# hacksaw_r0.net
KiCad netlist of a schematic drawn in EAGLE
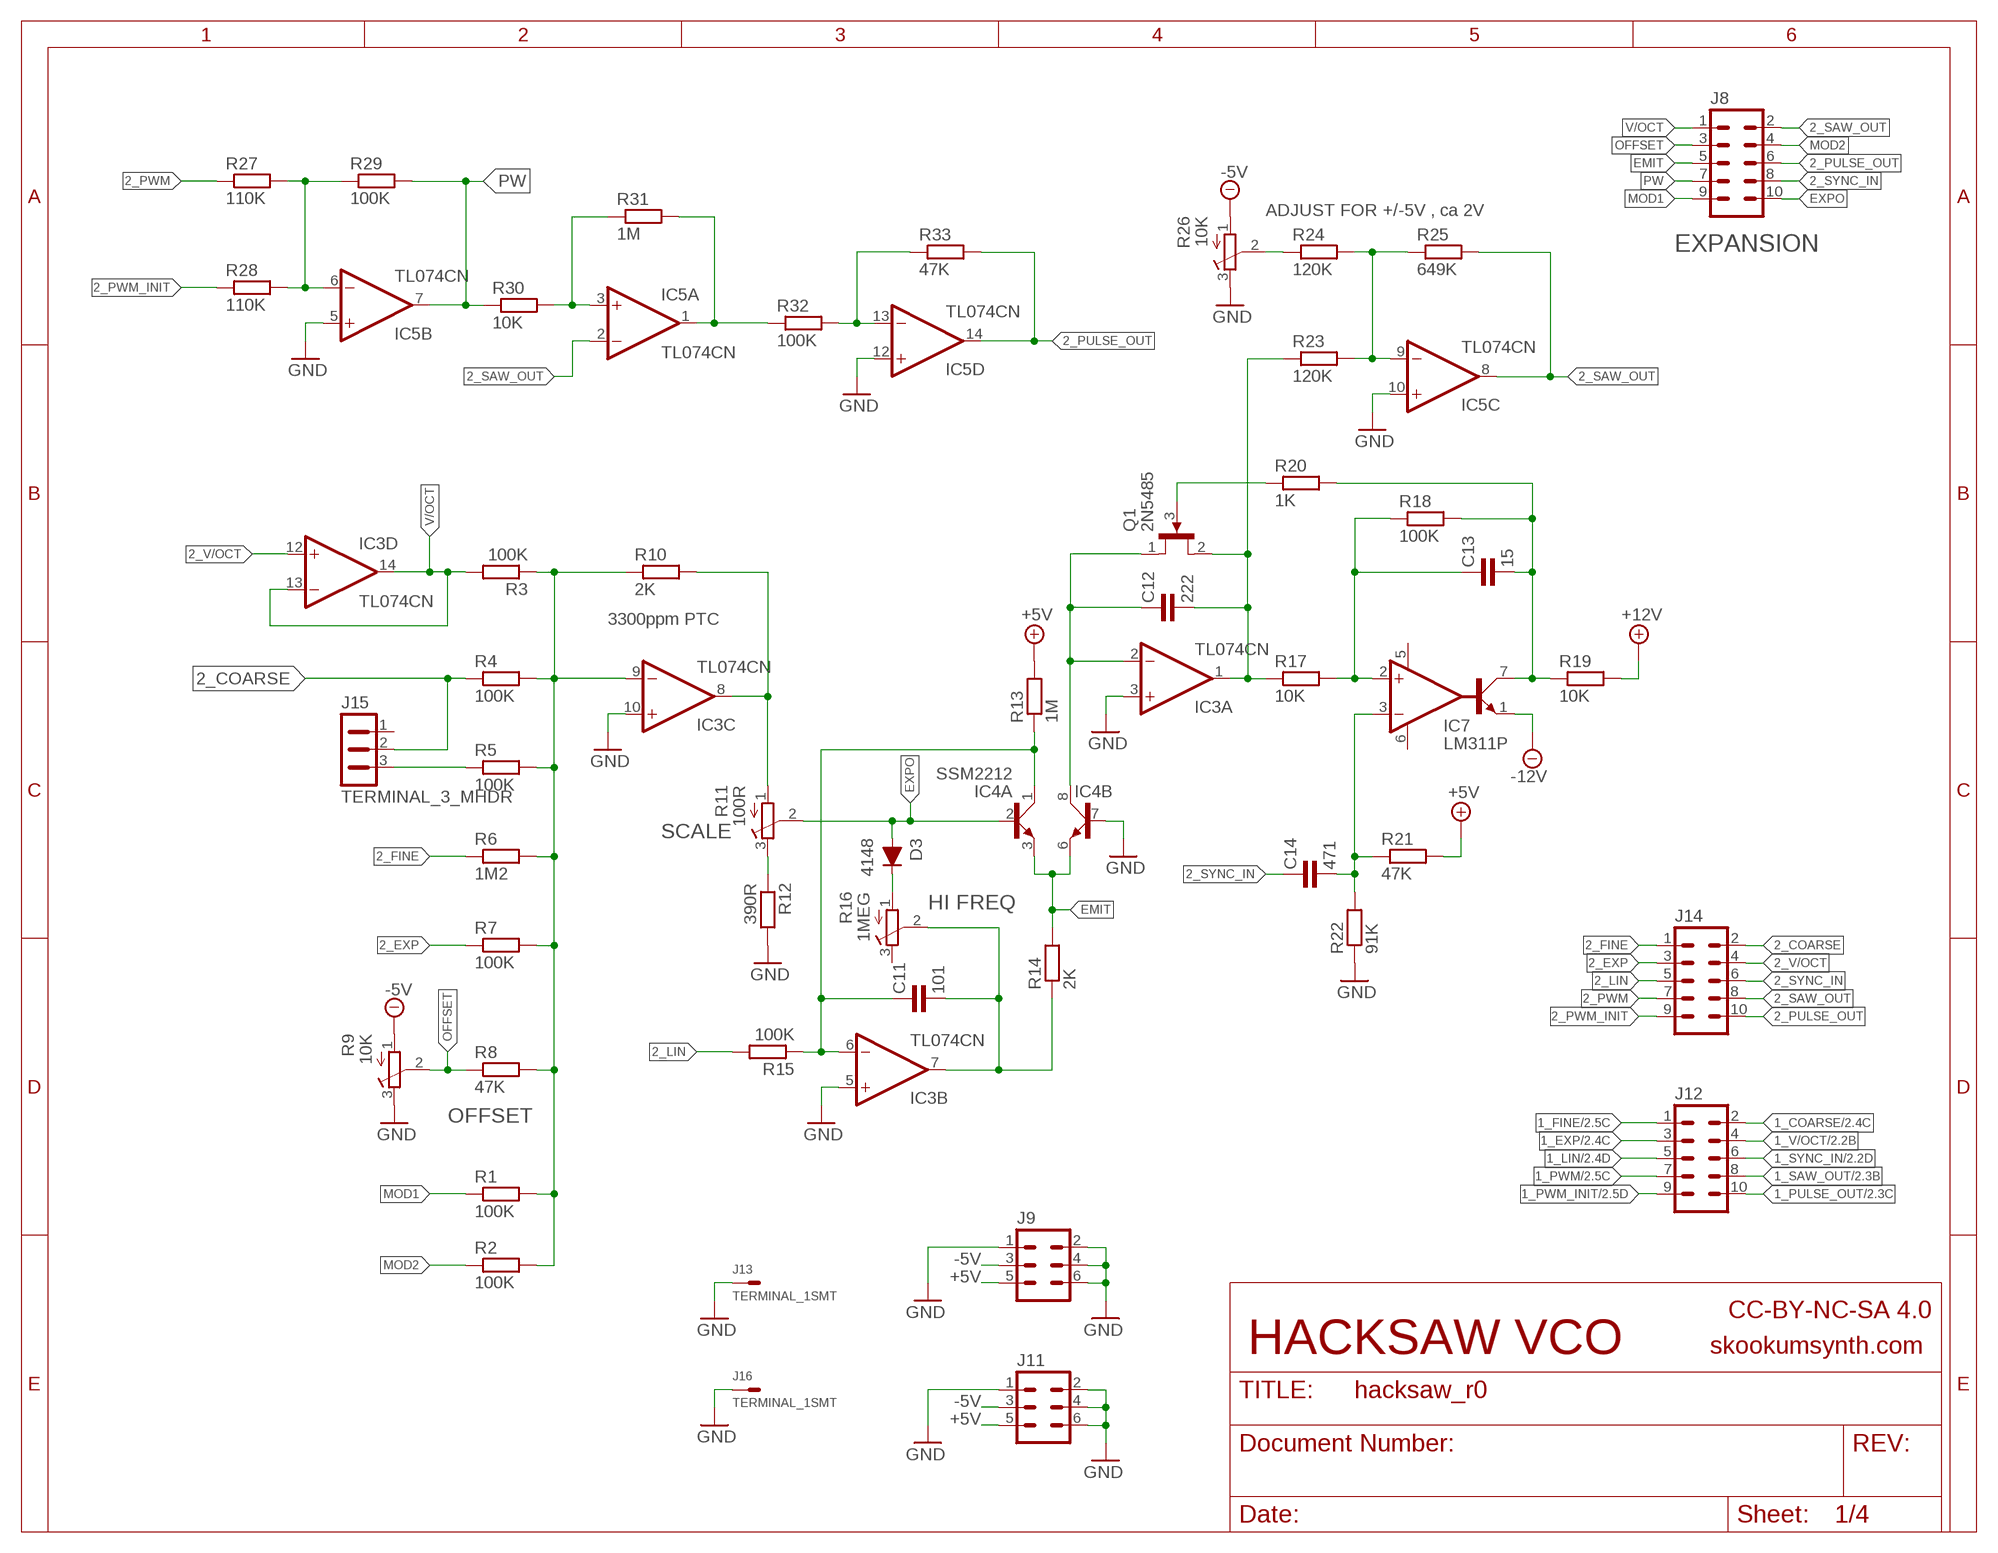
[diagram p0: schematic, sheet 1]
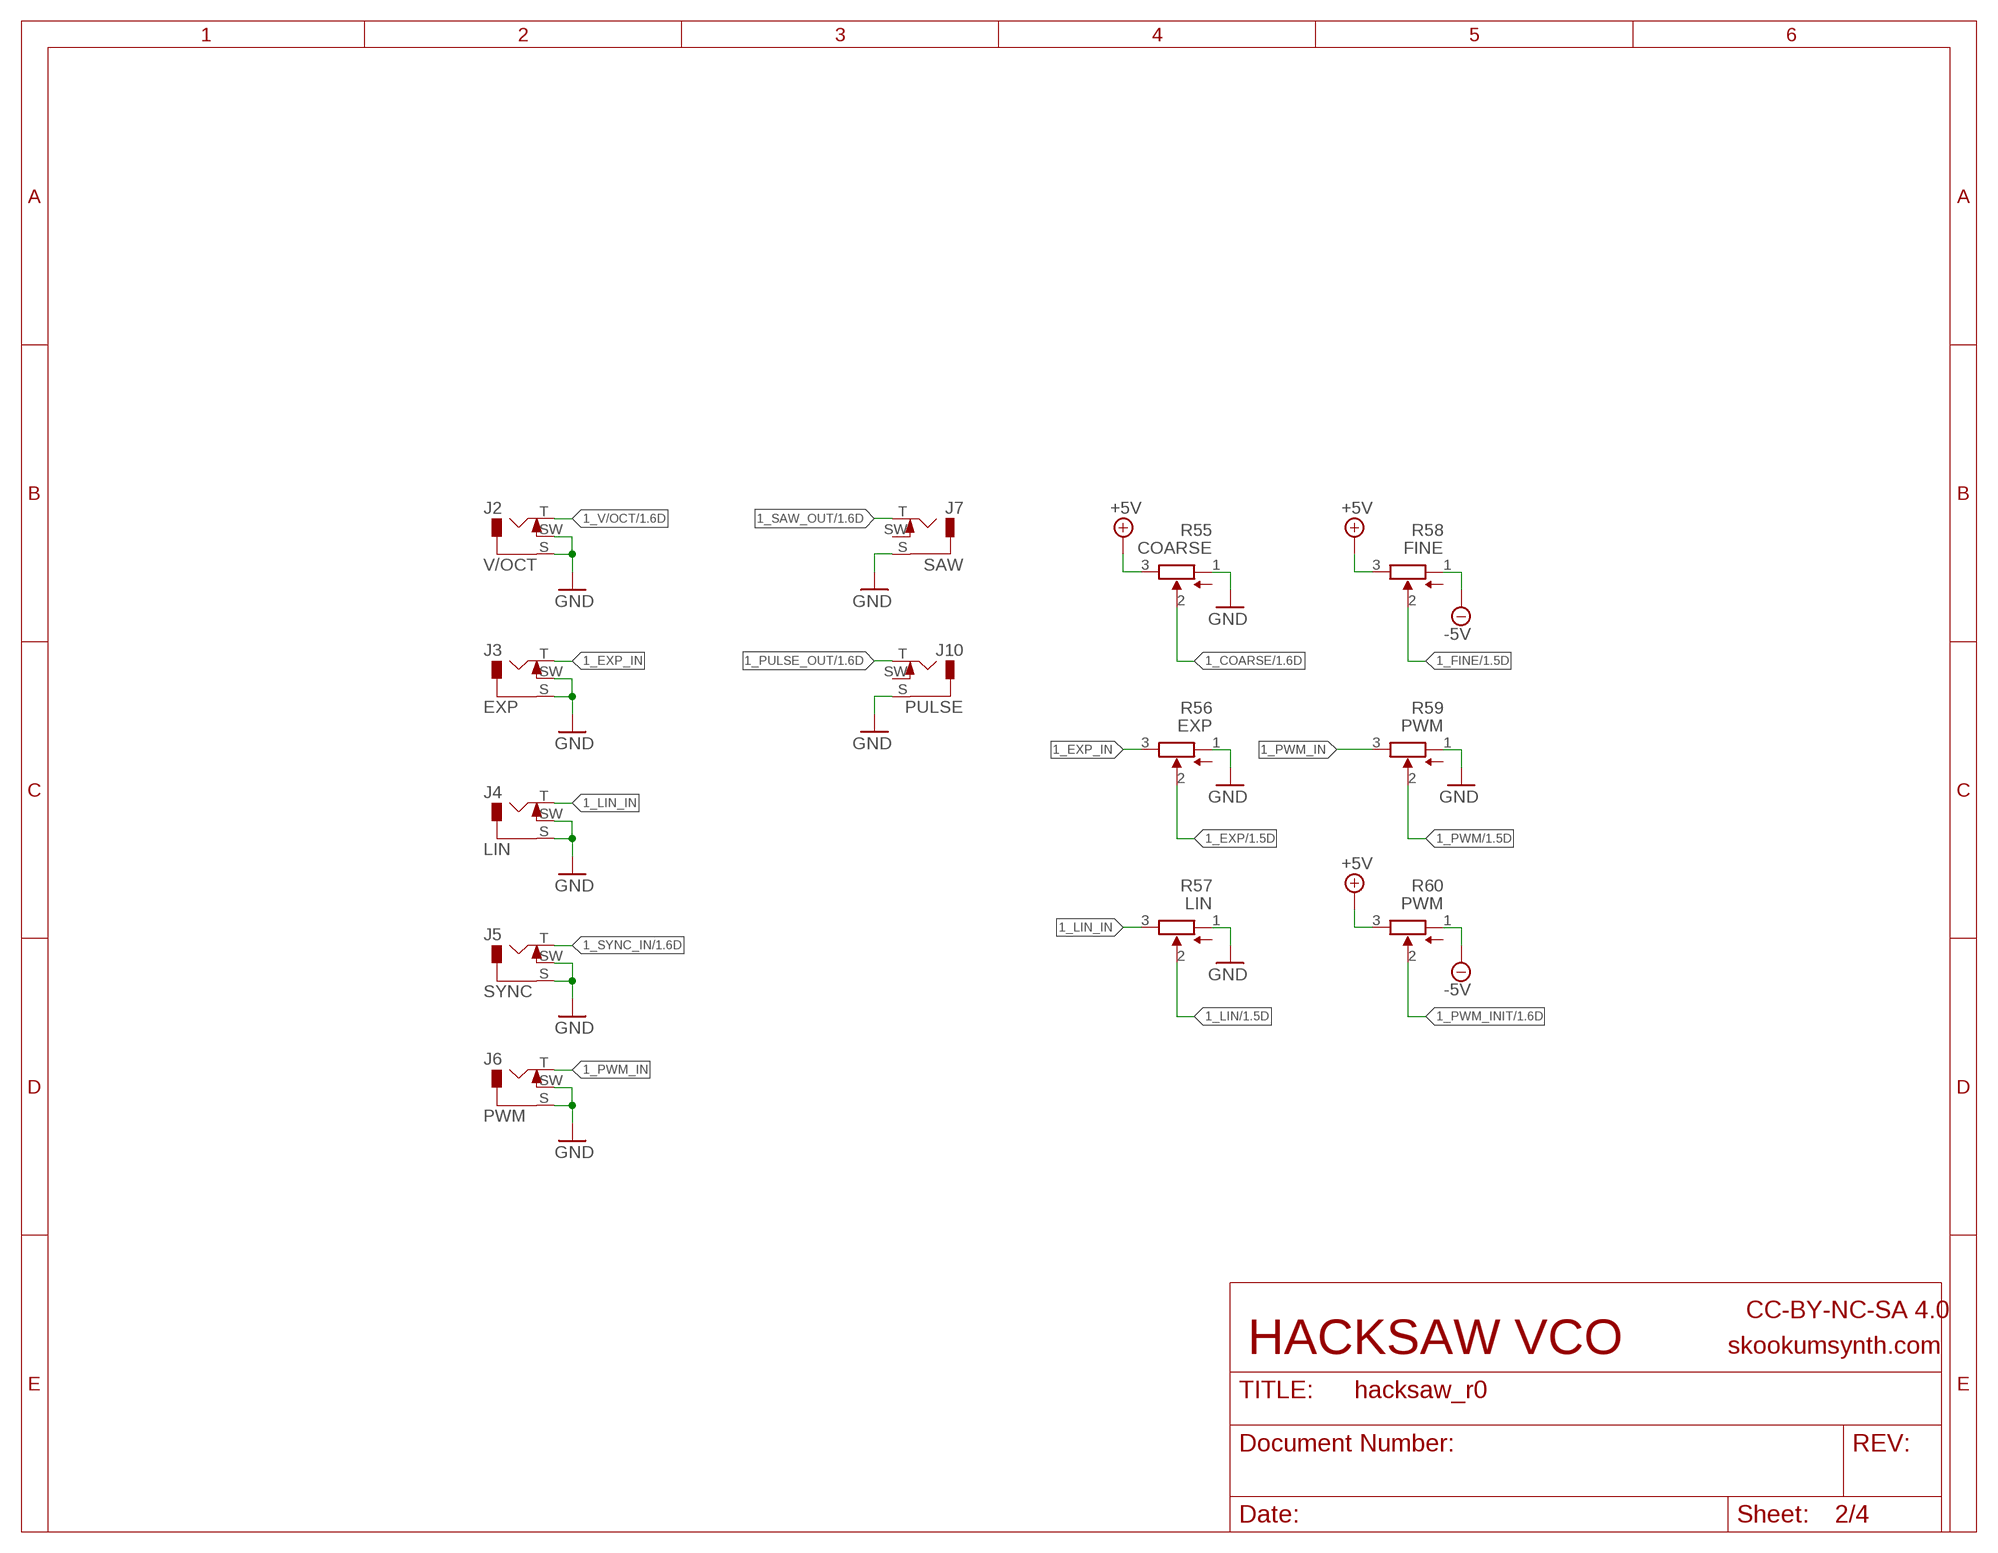
[diagram p1: schematic, sheet 2]
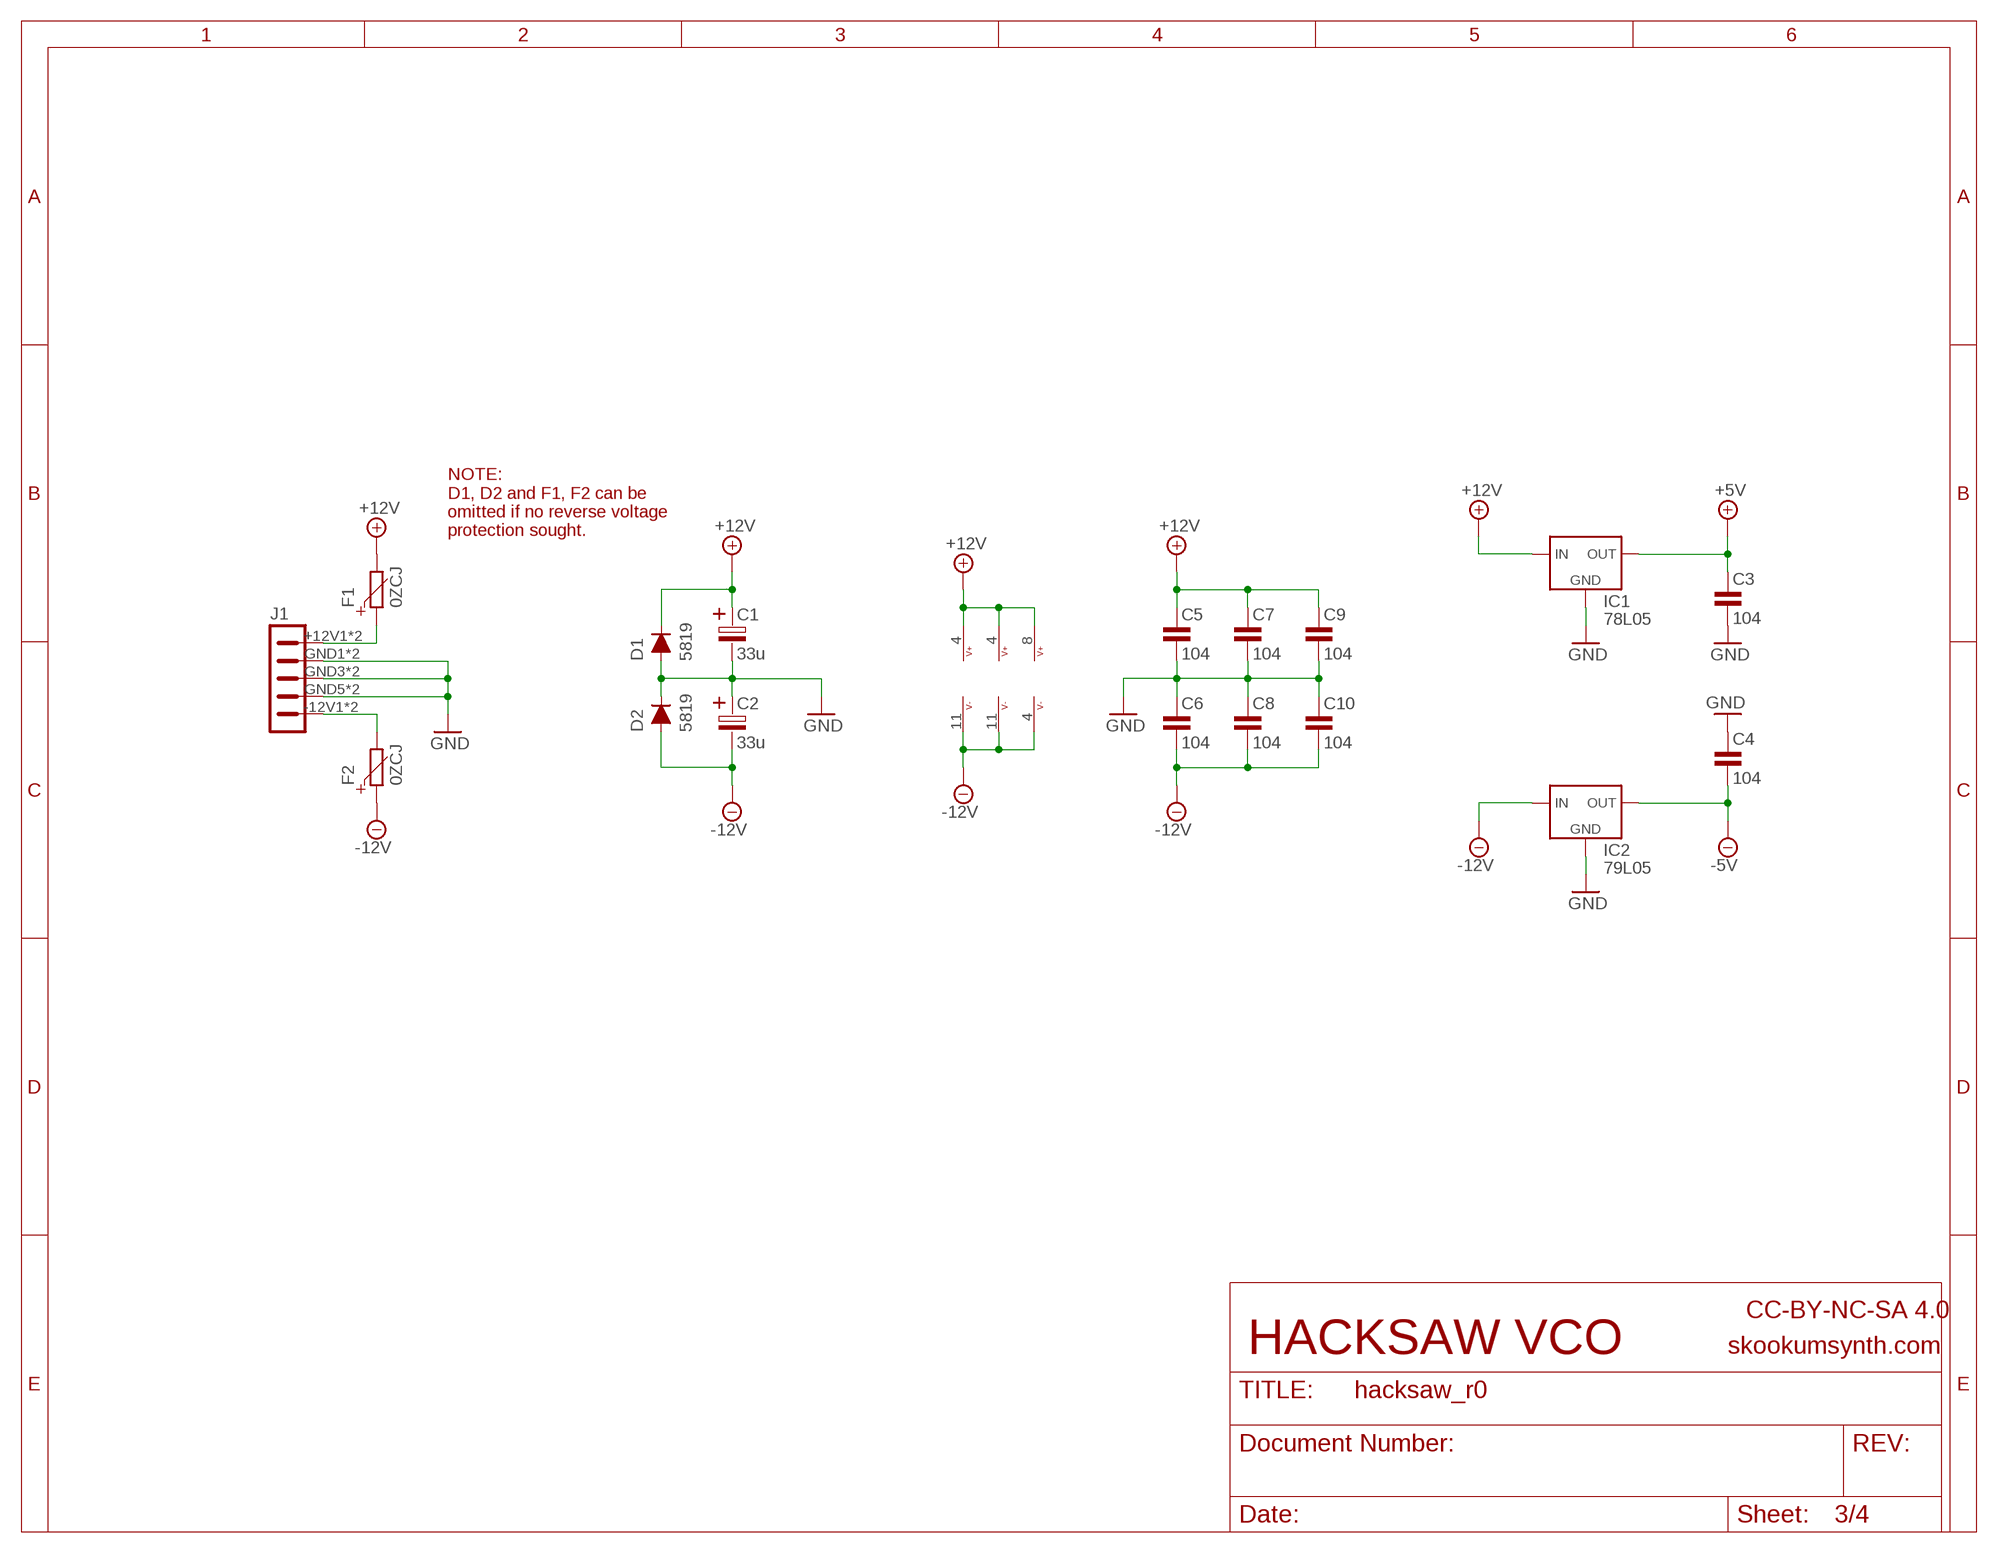
[diagram p2: schematic, sheet 3]
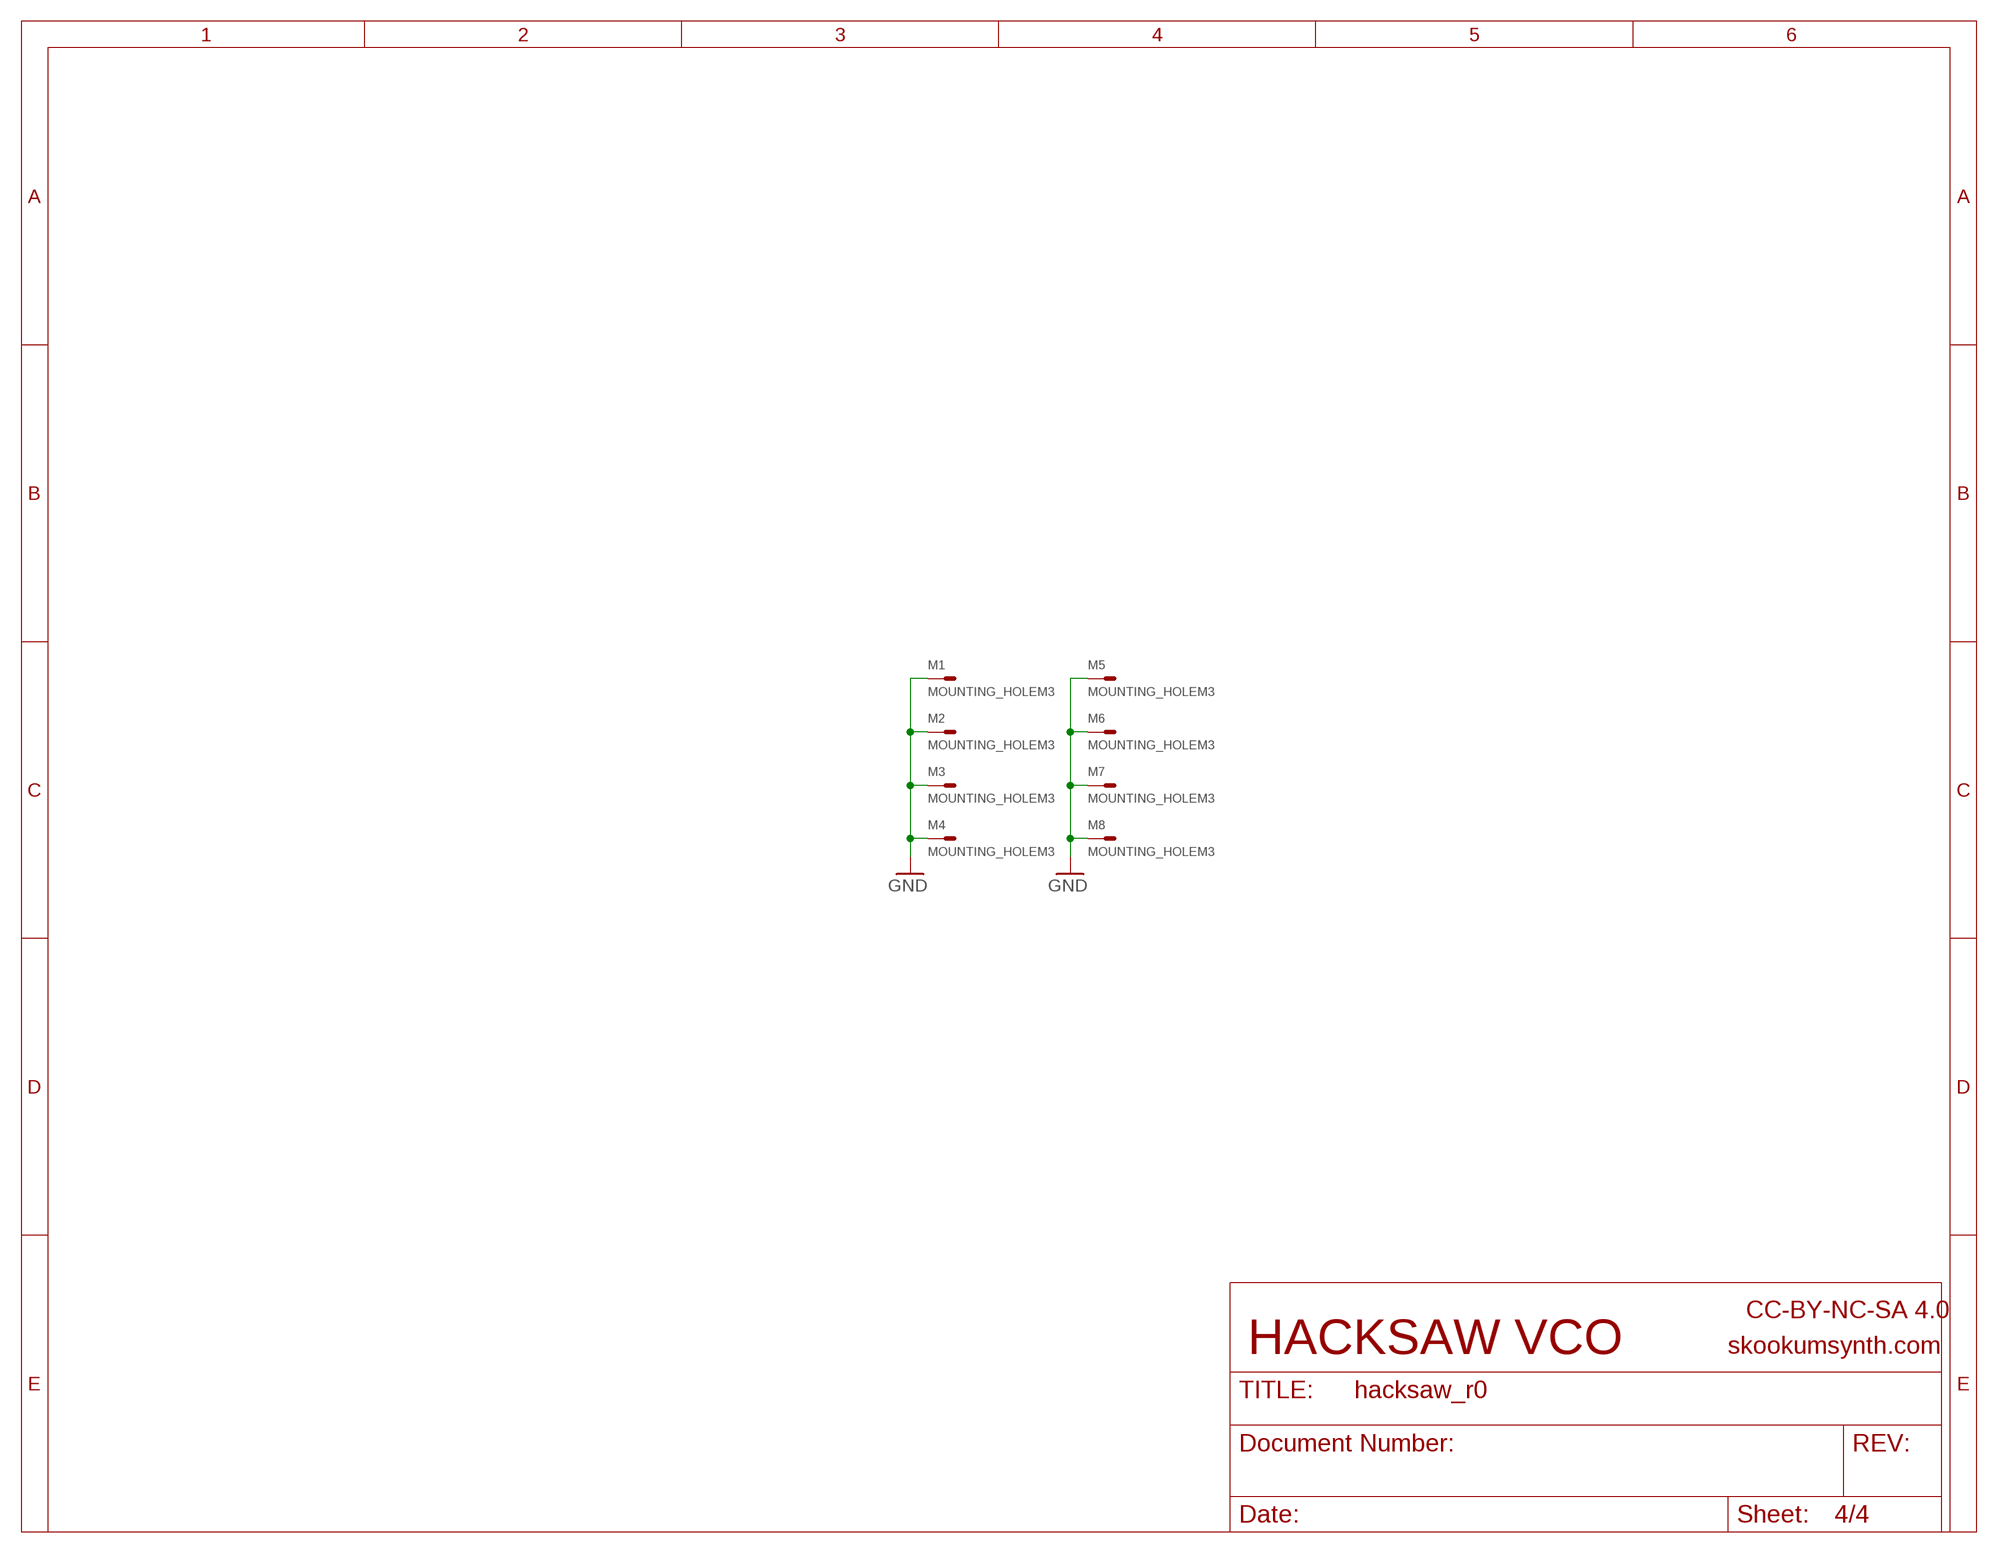
[diagram p3: schematic, sheet 4]

(export (version "E")
  (design (tool "Eeschema 10.0.6"))
  (components
    (comp (ref "C11")
      (value "101")
      (footprint "eagle-import:0805")
      (libsource (lib "eagle-import") (part "CAP_0805"))
    )
    (comp (ref "C12")
      (value "222")
      (footprint "eagle-import:PHE450")
      (libsource (lib "eagle-import") (part "CAP_PHE450"))
    )
    (comp (ref "C13")
      (value "15")
      (footprint "eagle-import:0805")
      (libsource (lib "eagle-import") (part "CAP_0805"))
    )
    (comp (ref "C14")
      (value "471")
      (footprint "eagle-import:0805")
      (libsource (lib "eagle-import") (part "CAP_0805"))
    )
    (comp (ref "D3")
      (value "4148")
      (footprint "eagle-import:SOD123")
      (libsource (lib "eagle-import") (part "DIODE_RECT_SOD123"))
    )
    (comp (ref "IC3")
      (value "TL074CN")
      (footprint "eagle-import:DIL14")
      (libsource (lib "eagle-import") (part "OPAMP_QUAD_DIL14"))
    )
    (comp (ref "IC4")
      (value "SSM2212")
      (footprint "eagle-import:DIL8")
      (libsource (lib "eagle-import") (part "SSM2212"))
    )
    (comp (ref "IC5")
      (value "TL074CN")
      (footprint "eagle-import:DIL14")
      (libsource (lib "eagle-import") (part "OPAMP_QUAD_DIL14"))
    )
    (comp (ref "IC7")
      (value "LM311P")
      (footprint "eagle-import:DIL8")
      (libsource (lib "eagle-import") (part "LM311P"))
    )
    (comp (ref "J8")
      (value "CONN_HDR_5X21")
      (footprint "eagle-import:HDR_M_5X2")
      (libsource (lib "eagle-import") (part "CONN_HDR_5X21"))
    )
    (comp (ref "J9")
      (value "CONN_HDR_3X21")
      (footprint "eagle-import:HDR_M_3X2")
      (libsource (lib "eagle-import") (part "CONN_HDR_3X21"))
    )
    (comp (ref "J11")
      (value "CONN_HDR_3X22")
      (footprint "eagle-import:HDR_M_3X2_REAR")
      (libsource (lib "eagle-import") (part "CONN_HDR_3X22"))
    )
    (comp (ref "J12")
      (value "CONN_HDR_5X22")
      (footprint "eagle-import:HDR_M_5X2_REAR")
      (libsource (lib "eagle-import") (part "CONN_HDR_5X22"))
    )
    (comp (ref "J13")
      (value "TERMINAL_1SMT")
      (footprint "eagle-import:FP_GND")
      (libsource (lib "eagle-import") (part "TERMINAL_1SMT"))
    )
    (comp (ref "J14")
      (value "CONN_HDR_5X21")
      (footprint "eagle-import:HDR_M_5X2")
      (libsource (lib "eagle-import") (part "CONN_HDR_5X21"))
    )
    (comp (ref "J15")
      (value "TERMINAL_3_MHDR")
      (footprint "eagle-import:HDR_M_3")
      (libsource (lib "eagle-import") (part "TERMINAL_3_MHDR"))
    )
    (comp (ref "J16")
      (value "TERMINAL_1SMT")
      (footprint "eagle-import:FP_GND")
      (libsource (lib "eagle-import") (part "TERMINAL_1SMT"))
    )
    (comp (ref "Q1")
      (value "2N5485")
      (footprint "eagle-import:TO-92_2")
      (libsource (lib "eagle-import") (part "NJFET_2N5485"))
    )
    (comp (ref "R1")
      (value "100K")
      (footprint "eagle-import:0805")
      (libsource (lib "eagle-import") (part "RESISTOR_0805"))
    )
    (comp (ref "R2")
      (value "100K")
      (footprint "eagle-import:0805")
      (libsource (lib "eagle-import") (part "RESISTOR_0805"))
    )
    (comp (ref "R3")
      (value "100K")
      (footprint "eagle-import:0805")
      (libsource (lib "eagle-import") (part "RESISTOR_0805"))
    )
    (comp (ref "R4")
      (value "100K")
      (footprint "eagle-import:0805")
      (libsource (lib "eagle-import") (part "RESISTOR_0805"))
    )
    (comp (ref "R5")
      (value "100K")
      (footprint "eagle-import:0805")
      (libsource (lib "eagle-import") (part "RESISTOR_0805"))
    )
    (comp (ref "R6")
      (value "1M2")
      (footprint "eagle-import:0805")
      (libsource (lib "eagle-import") (part "RESISTOR_0805"))
    )
    (comp (ref "R7")
      (value "100K")
      (footprint "eagle-import:0805")
      (libsource (lib "eagle-import") (part "RESISTOR_0805"))
    )
    (comp (ref "R8")
      (value "47K")
      (footprint "eagle-import:0805")
      (libsource (lib "eagle-import") (part "RESISTOR_0805"))
    )
    (comp (ref "R9")
      (value "10K")
      (footprint "eagle-import:PV36W")
      (libsource (lib "eagle-import") (part "RESISTOR_TRIM_PV36W"))
    )
    (comp (ref "R10")
      (value "2K")
      (footprint "eagle-import:RESISTOR_TH_1_4W")
      (libsource (lib "eagle-import") (part "RESISTOR_1/4W"))
    )
    (comp (ref "R11")
      (value "100R")
      (footprint "eagle-import:PV36W")
      (libsource (lib "eagle-import") (part "RESISTOR_TRIM_PV36W"))
    )
    (comp (ref "R12")
      (value "390R")
      (footprint "eagle-import:0805")
      (libsource (lib "eagle-import") (part "RESISTOR_0805"))
    )
    (comp (ref "R13")
      (value "1M")
      (footprint "eagle-import:0805")
      (libsource (lib "eagle-import") (part "RESISTOR_0805"))
    )
    (comp (ref "R14")
      (value "2K")
      (footprint "eagle-import:0805")
      (libsource (lib "eagle-import") (part "RESISTOR_0805"))
    )
    (comp (ref "R15")
      (value "100K")
      (footprint "eagle-import:0805")
      (libsource (lib "eagle-import") (part "RESISTOR_0805"))
    )
    (comp (ref "R16")
      (value "1MEG")
      (footprint "eagle-import:PV36W")
      (libsource (lib "eagle-import") (part "RESISTOR_TRIM_PV36W"))
    )
    (comp (ref "R17")
      (value "10K")
      (footprint "eagle-import:0805")
      (libsource (lib "eagle-import") (part "RESISTOR_0805"))
    )
    (comp (ref "R18")
      (value "100K")
      (footprint "eagle-import:0805")
      (libsource (lib "eagle-import") (part "RESISTOR_0805"))
    )
    (comp (ref "R19")
      (value "10K")
      (footprint "eagle-import:0805")
      (libsource (lib "eagle-import") (part "RESISTOR_0805"))
    )
    (comp (ref "R20")
      (value "1K")
      (footprint "eagle-import:0805")
      (libsource (lib "eagle-import") (part "RESISTOR_0805"))
    )
    (comp (ref "R21")
      (value "47K")
      (footprint "eagle-import:0805")
      (libsource (lib "eagle-import") (part "RESISTOR_0805"))
    )
    (comp (ref "R22")
      (value "91K")
      (footprint "eagle-import:0805")
      (libsource (lib "eagle-import") (part "RESISTOR_0805"))
    )
    (comp (ref "R23")
      (value "120K")
      (footprint "eagle-import:0805")
      (libsource (lib "eagle-import") (part "RESISTOR_0805"))
    )
    (comp (ref "R24")
      (value "120K")
      (footprint "eagle-import:0805")
      (libsource (lib "eagle-import") (part "RESISTOR_0805"))
    )
    (comp (ref "R25")
      (value "649K")
      (footprint "eagle-import:0805")
      (libsource (lib "eagle-import") (part "RESISTOR_0805"))
    )
    (comp (ref "R26")
      (value "10K")
      (footprint "eagle-import:PV36W")
      (libsource (lib "eagle-import") (part "RESISTOR_TRIM_PV36W"))
    )
    (comp (ref "R27")
      (value "110K")
      (footprint "eagle-import:0805")
      (libsource (lib "eagle-import") (part "RESISTOR_0805"))
    )
    (comp (ref "R28")
      (value "110K")
      (footprint "eagle-import:0805")
      (libsource (lib "eagle-import") (part "RESISTOR_0805"))
    )
    (comp (ref "R29")
      (value "100K")
      (footprint "eagle-import:0805")
      (libsource (lib "eagle-import") (part "RESISTOR_0805"))
    )
    (comp (ref "R30")
      (value "10K")
      (footprint "eagle-import:0805")
      (libsource (lib "eagle-import") (part "RESISTOR_0805"))
    )
    (comp (ref "R31")
      (value "1M")
      (footprint "eagle-import:0805")
      (libsource (lib "eagle-import") (part "RESISTOR_0805"))
    )
    (comp (ref "R32")
      (value "100K")
      (footprint "eagle-import:0805")
      (libsource (lib "eagle-import") (part "RESISTOR_0805"))
    )
    (comp (ref "R33")
      (value "47K")
      (footprint "eagle-import:0805")
      (libsource (lib "eagle-import") (part "RESISTOR_0805"))
    )
    (comp (ref "J2")
      (value "V/OCT")
      (footprint "eagle-import:WQP_PJ301M-12")
      (libsource (lib "eagle-import") (part "CONN_MONO_SW_F_V"))
    )
    (comp (ref "J3")
      (value "EXP")
      (footprint "eagle-import:WQP_PJ301M-12")
      (libsource (lib "eagle-import") (part "CONN_MONO_SW_F_V"))
    )
    (comp (ref "J4")
      (value "LIN")
      (footprint "eagle-import:WQP_PJ301M-12")
      (libsource (lib "eagle-import") (part "CONN_MONO_SW_F_V"))
    )
    (comp (ref "J5")
      (value "SYNC")
      (footprint "eagle-import:WQP_PJ301M-12")
      (libsource (lib "eagle-import") (part "CONN_MONO_SW_F_V"))
    )
    (comp (ref "J6")
      (value "PWM")
      (footprint "eagle-import:WQP_PJ301M-12")
      (libsource (lib "eagle-import") (part "CONN_MONO_SW_F_V"))
    )
    (comp (ref "J7")
      (value "SAW")
      (footprint "eagle-import:WQP_PJ301M-12")
      (libsource (lib "eagle-import") (part "CONN_MONO_SW_F_V"))
    )
    (comp (ref "J10")
      (value "PULSE")
      (footprint "eagle-import:WQP_PJ301M-12")
      (libsource (lib "eagle-import") (part "CONN_MONO_SW_F_V"))
    )
    (comp (ref "R55")
      (value "COARSE")
      (footprint "eagle-import:PTV09")
      (libsource (lib "eagle-import") (part "POTENTIOMETER-A6"))
    )
    (comp (ref "R56")
      (value "EXP")
      (footprint "eagle-import:PTV09")
      (libsource (lib "eagle-import") (part "POTENTIOMETER-A6"))
    )
    (comp (ref "R57")
      (value "LIN")
      (footprint "eagle-import:PTV09")
      (libsource (lib "eagle-import") (part "POTENTIOMETER-A6"))
    )
    (comp (ref "R58")
      (value "FINE")
      (footprint "eagle-import:PTV09")
      (libsource (lib "eagle-import") (part "POTENTIOMETER-A6"))
    )
    (comp (ref "R59")
      (value "PWM")
      (footprint "eagle-import:PTV09")
      (libsource (lib "eagle-import") (part "POTENTIOMETER-A6"))
    )
    (comp (ref "R60")
      (value "PWM")
      (footprint "eagle-import:PTV09")
      (libsource (lib "eagle-import") (part "POTENTIOMETER-A6"))
    )
    (comp (ref "C1")
      (value "33u")
      (footprint "eagle-import:CAP_POL_2.5-6")
      (libsource (lib "eagle-import") (part "CAP_POL_PTH_2.5-6"))
    )
    (comp (ref "C2")
      (value "33u")
      (footprint "eagle-import:CAP_POL_2.5-6")
      (libsource (lib "eagle-import") (part "CAP_POL_PTH_2.5-6"))
    )
    (comp (ref "C3")
      (value "104")
      (footprint "eagle-import:0805")
      (libsource (lib "eagle-import") (part "CAP_0805"))
    )
    (comp (ref "C4")
      (value "104")
      (footprint "eagle-import:0805")
      (libsource (lib "eagle-import") (part "CAP_0805"))
    )
    (comp (ref "C5")
      (value "104")
      (footprint "eagle-import:0805")
      (libsource (lib "eagle-import") (part "CAP_0805"))
    )
    (comp (ref "C6")
      (value "104")
      (footprint "eagle-import:0805")
      (libsource (lib "eagle-import") (part "CAP_0805"))
    )
    (comp (ref "C7")
      (value "104")
      (footprint "eagle-import:0805")
      (libsource (lib "eagle-import") (part "CAP_0805"))
    )
    (comp (ref "C8")
      (value "104")
      (footprint "eagle-import:0805")
      (libsource (lib "eagle-import") (part "CAP_0805"))
    )
    (comp (ref "C9")
      (value "104")
      (footprint "eagle-import:0805")
      (libsource (lib "eagle-import") (part "CAP_0805"))
    )
    (comp (ref "C10")
      (value "104")
      (footprint "eagle-import:0805")
      (libsource (lib "eagle-import") (part "CAP_0805"))
    )
    (comp (ref "D1")
      (value "5819")
      (footprint "eagle-import:SOD123")
      (libsource (lib "eagle-import") (part "DIODE_RECT_SOD123"))
    )
    (comp (ref "D2")
      (value "5819")
      (footprint "eagle-import:SOD123")
      (libsource (lib "eagle-import") (part "DIODE_RECT_SOD123"))
    )
    (comp (ref "F1")
      (value "0ZCJ")
      (footprint "eagle-import:1206")
      (libsource (lib "eagle-import") (part "PTC_0ZCJ"))
    )
    (comp (ref "F2")
      (value "0ZCJ")
      (footprint "eagle-import:1206")
      (libsource (lib "eagle-import") (part "PTC_0ZCJ"))
    )
    (comp (ref "IC1")
      (value "78L05")
      (footprint "eagle-import:TO-92_2")
      (libsource (lib "eagle-import") (part "78LXXACLPR"))
    )
    (comp (ref "IC2")
      (value "79L05")
      (footprint "eagle-import:TO-92_2")
      (libsource (lib "eagle-import") (part "79LXXACLPR"))
    )
    (comp (ref "J1")
      (value "HDR_POWER_10_VERT")
      (footprint "eagle-import:HDR_POWER_10")
      (libsource (lib "eagle-import") (part "HDR_POWER_10_VERT"))
    )
    (comp (ref "M1")
      (value "MOUNTING_HOLEM3")
      (footprint "eagle-import:M3")
      (libsource (lib "eagle-import") (part "MOUNTING_HOLEM3"))
    )
    (comp (ref "M2")
      (value "MOUNTING_HOLEM3")
      (footprint "eagle-import:M3")
      (libsource (lib "eagle-import") (part "MOUNTING_HOLEM3"))
    )
    (comp (ref "M3")
      (value "MOUNTING_HOLEM3")
      (footprint "eagle-import:M3")
      (libsource (lib "eagle-import") (part "MOUNTING_HOLEM3"))
    )
    (comp (ref "M4")
      (value "MOUNTING_HOLEM3")
      (footprint "eagle-import:M3")
      (libsource (lib "eagle-import") (part "MOUNTING_HOLEM3"))
    )
    (comp (ref "M5")
      (value "MOUNTING_HOLEM3")
      (footprint "eagle-import:M3")
      (libsource (lib "eagle-import") (part "MOUNTING_HOLEM3"))
    )
    (comp (ref "M6")
      (value "MOUNTING_HOLEM3")
      (footprint "eagle-import:M3")
      (libsource (lib "eagle-import") (part "MOUNTING_HOLEM3"))
    )
    (comp (ref "M7")
      (value "MOUNTING_HOLEM3")
      (footprint "eagle-import:M3")
      (libsource (lib "eagle-import") (part "MOUNTING_HOLEM3"))
    )
    (comp (ref "M8")
      (value "MOUNTING_HOLEM3")
      (footprint "eagle-import:M3")
      (libsource (lib "eagle-import") (part "MOUNTING_HOLEM3"))
    )
  )
  (nets
    (net (code "1") (name "+5V") (class "Default")
      (node (ref "C3") (pin "1") (pinfunction "+_1") (pintype "passive"))
      (node (ref "IC1") (pin "1") (pinfunction "OUT_1") (pintype "power_in"))
      (node (ref "J11") (pin "5") (pinfunction "5_5") (pintype "passive"))
      (node (ref "J9") (pin "5") (pinfunction "5_5") (pintype "passive"))
      (node (ref "R13") (pin "2") (pinfunction "2_2") (pintype "passive"))
      (node (ref "R21") (pin "2") (pinfunction "2_2") (pintype "passive"))
      (node (ref "R55") (pin "3") (pinfunction "3_3") (pintype "passive"))
      (node (ref "R58") (pin "3") (pinfunction "3_3") (pintype "passive"))
      (node (ref "R60") (pin "3") (pinfunction "3_3") (pintype "passive"))
    )
    (net (code "2") (name "+12V") (class "Default")
      (node (ref "C1") (pin "+") (pinfunction "+_+") (pintype "passive"))
      (node (ref "C5") (pin "1") (pinfunction "+_1") (pintype "passive"))
      (node (ref "C7") (pin "1") (pinfunction "+_1") (pintype "passive"))
      (node (ref "C9") (pin "1") (pinfunction "+_1") (pintype "passive"))
      (node (ref "D1") (pin "K") (pinfunction "C_K") (pintype "passive"))
      (node (ref "F1") (pin "2") (pinfunction "2_2") (pintype "passive"))
      (node (ref "IC1") (pin "3") (pinfunction "IN_3") (pintype "power_in"))
      (node (ref "IC3") (pin "4") (pinfunction "V+_4") (pintype "power_in"))
      (node (ref "IC5") (pin "4") (pinfunction "V+_4") (pintype "power_in"))
      (node (ref "IC7") (pin "8") (pinfunction "V+_8") (pintype "power_in"))
      (node (ref "R19") (pin "2") (pinfunction "2_2") (pintype "passive"))
    )
    (net (code "3") (name "-5V") (class "Default")
      (node (ref "C4") (pin "2") (pinfunction "-_2") (pintype "passive"))
      (node (ref "IC2") (pin "3") (pinfunction "OUT_3") (pintype "power_in"))
      (node (ref "J11") (pin "3") (pinfunction "3_3") (pintype "passive"))
      (node (ref "J9") (pin "3") (pinfunction "3_3") (pintype "passive"))
      (node (ref "R26") (pin "1") (pinfunction "1_1") (pintype "passive"))
      (node (ref "R58") (pin "1") (pinfunction "1_1") (pintype "passive"))
      (node (ref "R60") (pin "1") (pinfunction "1_1") (pintype "passive"))
      (node (ref "R9") (pin "1") (pinfunction "1_1") (pintype "passive"))
    )
    (net (code "4") (name "-12V") (class "Default")
      (node (ref "C10") (pin "2") (pinfunction "-_2") (pintype "passive"))
      (node (ref "C2") (pin "-") (pinfunction "-_-") (pintype "passive"))
      (node (ref "C6") (pin "2") (pinfunction "-_2") (pintype "passive"))
      (node (ref "C8") (pin "2") (pinfunction "-_2") (pintype "passive"))
      (node (ref "D2") (pin "A") (pinfunction "A_A") (pintype "passive"))
      (node (ref "F2") (pin "1") (pinfunction "1_1") (pintype "passive"))
      (node (ref "IC2") (pin "2") (pinfunction "IN_2") (pintype "power_in"))
      (node (ref "IC3") (pin "11") (pinfunction "V-_11") (pintype "power_in"))
      (node (ref "IC5") (pin "11") (pinfunction "V-_11") (pintype "power_in"))
      (node (ref "IC7") (pin "1") (pinfunction "EMIT_1") (pintype "bidirectional"))
      (node (ref "IC7") (pin "4") (pinfunction "V-_4") (pintype "power_in"))
    )
    (net (code "5") (name "1_COARSE") (class "Default")
      (node (ref "J12") (pin "2") (pinfunction "2_2") (pintype "passive"))
      (node (ref "R55") (pin "2") (pinfunction "2_2") (pintype "passive"))
    )
    (net (code "6") (name "1_EXP") (class "Default")
      (node (ref "J12") (pin "3") (pinfunction "3_3") (pintype "passive"))
      (node (ref "R56") (pin "2") (pinfunction "2_2") (pintype "passive"))
    )
    (net (code "7") (name "1_EXP_IN") (class "Default")
      (node (ref "J3") (pin "T") (pinfunction "T_T") (pintype "bidirectional"))
      (node (ref "R56") (pin "3") (pinfunction "3_3") (pintype "passive"))
    )
    (net (code "8") (name "1_FINE") (class "Default")
      (node (ref "J12") (pin "1") (pinfunction "1_1") (pintype "passive"))
      (node (ref "R58") (pin "2") (pinfunction "2_2") (pintype "passive"))
    )
    (net (code "9") (name "1_LIN") (class "Default")
      (node (ref "J12") (pin "5") (pinfunction "5_5") (pintype "passive"))
      (node (ref "R57") (pin "2") (pinfunction "2_2") (pintype "passive"))
    )
    (net (code "10") (name "1_LIN_IN") (class "Default")
      (node (ref "J4") (pin "T") (pinfunction "T_T") (pintype "bidirectional"))
      (node (ref "R57") (pin "3") (pinfunction "3_3") (pintype "passive"))
    )
    (net (code "11") (name "1_PULSE_OUT") (class "Default")
      (node (ref "J10") (pin "T") (pinfunction "T_T") (pintype "bidirectional"))
      (node (ref "J12") (pin "10") (pinfunction "10_10") (pintype "passive"))
    )
    (net (code "12") (name "1_PWM") (class "Default")
      (node (ref "J12") (pin "7") (pinfunction "7_7") (pintype "passive"))
      (node (ref "R59") (pin "2") (pinfunction "2_2") (pintype "passive"))
    )
    (net (code "13") (name "1_PWM_IN") (class "Default")
      (node (ref "J6") (pin "T") (pinfunction "T_T") (pintype "bidirectional"))
      (node (ref "R59") (pin "3") (pinfunction "3_3") (pintype "passive"))
    )
    (net (code "14") (name "1_PWM_INIT") (class "Default")
      (node (ref "J12") (pin "9") (pinfunction "9_9") (pintype "passive"))
      (node (ref "R60") (pin "2") (pinfunction "2_2") (pintype "passive"))
    )
    (net (code "15") (name "1_SAW_OUT") (class "Default")
      (node (ref "J12") (pin "8") (pinfunction "8_8") (pintype "passive"))
      (node (ref "J7") (pin "T") (pinfunction "T_T") (pintype "bidirectional"))
    )
    (net (code "16") (name "1_SYNC_IN") (class "Default")
      (node (ref "J12") (pin "6") (pinfunction "6_6") (pintype "passive"))
      (node (ref "J5") (pin "T") (pinfunction "T_T") (pintype "bidirectional"))
    )
    (net (code "17") (name "1_V{slash}OCT") (class "Default")
      (node (ref "J12") (pin "4") (pinfunction "4_4") (pintype "passive"))
      (node (ref "J2") (pin "T") (pinfunction "T_T") (pintype "bidirectional"))
    )
    (net (code "18") (name "2_COARSE") (class "Default")
      (node (ref "J14") (pin "2") (pinfunction "2_2") (pintype "passive"))
      (node (ref "J15") (pin "2") (pinfunction "2_2") (pintype "passive"))
      (node (ref "R4") (pin "1") (pinfunction "1_1") (pintype "passive"))
    )
    (net (code "19") (name "2_EXP") (class "Default")
      (node (ref "J14") (pin "3") (pinfunction "3_3") (pintype "passive"))
      (node (ref "R7") (pin "1") (pinfunction "1_1") (pintype "passive"))
    )
    (net (code "20") (name "2_FINE") (class "Default")
      (node (ref "J14") (pin "1") (pinfunction "1_1") (pintype "passive"))
      (node (ref "R6") (pin "1") (pinfunction "1_1") (pintype "passive"))
    )
    (net (code "21") (name "2_LIN") (class "Default")
      (node (ref "J14") (pin "5") (pinfunction "5_5") (pintype "passive"))
      (node (ref "R15") (pin "2") (pinfunction "2_2") (pintype "passive"))
    )
    (net (code "22") (name "2_PULSE_OUT") (class "Default")
      (node (ref "IC5") (pin "14") (pinfunction "OUT_14") (pintype "output"))
      (node (ref "J14") (pin "10") (pinfunction "10_10") (pintype "passive"))
      (node (ref "J8") (pin "6") (pinfunction "6_6") (pintype "passive"))
      (node (ref "R33") (pin "2") (pinfunction "2_2") (pintype "passive"))
    )
    (net (code "23") (name "2_PWM") (class "Default")
      (node (ref "J14") (pin "7") (pinfunction "7_7") (pintype "passive"))
      (node (ref "R27") (pin "1") (pinfunction "1_1") (pintype "passive"))
    )
    (net (code "24") (name "2_PWM_INIT") (class "Default")
      (node (ref "J14") (pin "9") (pinfunction "9_9") (pintype "passive"))
      (node (ref "R28") (pin "1") (pinfunction "1_1") (pintype "passive"))
    )
    (net (code "25") (name "2_SAW_OUT") (class "Default")
      (node (ref "IC5") (pin "2") (pinfunction "-IN_2") (pintype "input"))
      (node (ref "IC5") (pin "8") (pinfunction "OUT_8") (pintype "output"))
      (node (ref "J14") (pin "8") (pinfunction "8_8") (pintype "passive"))
      (node (ref "J8") (pin "2") (pinfunction "2_2") (pintype "passive"))
      (node (ref "R25") (pin "2") (pinfunction "2_2") (pintype "passive"))
    )
    (net (code "26") (name "2_SYNC_IN") (class "Default")
      (node (ref "C14") (pin "1") (pinfunction "+_1") (pintype "passive"))
      (node (ref "J14") (pin "6") (pinfunction "6_6") (pintype "passive"))
      (node (ref "J8") (pin "8") (pinfunction "8_8") (pintype "passive"))
    )
    (net (code "27") (name "2_V{slash}OCT") (class "Default")
      (node (ref "IC3") (pin "12") (pinfunction "+IN_12") (pintype "input"))
      (node (ref "J14") (pin "4") (pinfunction "4_4") (pintype "passive"))
    )
    (net (code "28") (name "EMIT") (class "Default")
      (node (ref "IC4") (pin "3") (pinfunction "E_3") (pintype "passive"))
      (node (ref "IC4") (pin "6") (pinfunction "E_6") (pintype "passive"))
      (node (ref "J8") (pin "5") (pinfunction "5_5") (pintype "passive"))
      (node (ref "R14") (pin "2") (pinfunction "2_2") (pintype "passive"))
    )
    (net (code "29") (name "EXPO") (class "Default")
      (node (ref "D3") (pin "A") (pinfunction "A_A") (pintype "passive"))
      (node (ref "IC4") (pin "2") (pinfunction "B_2") (pintype "passive"))
      (node (ref "J8") (pin "10") (pinfunction "10_10") (pintype "passive"))
      (node (ref "R11") (pin "2") (pinfunction "2_2") (pintype "passive"))
    )
    (net (code "30") (name "GND") (class "Default")
      (node (ref "C1") (pin "-") (pinfunction "-_-") (pintype "passive"))
      (node (ref "C10") (pin "1") (pinfunction "+_1") (pintype "passive"))
      (node (ref "C2") (pin "+") (pinfunction "+_+") (pintype "passive"))
      (node (ref "C3") (pin "2") (pinfunction "-_2") (pintype "passive"))
      (node (ref "C4") (pin "1") (pinfunction "+_1") (pintype "passive"))
      (node (ref "C5") (pin "2") (pinfunction "-_2") (pintype "passive"))
      (node (ref "C6") (pin "1") (pinfunction "+_1") (pintype "passive"))
      (node (ref "C7") (pin "2") (pinfunction "-_2") (pintype "passive"))
      (node (ref "C8") (pin "1") (pinfunction "+_1") (pintype "passive"))
      (node (ref "C9") (pin "2") (pinfunction "-_2") (pintype "passive"))
      (node (ref "D1") (pin "A") (pinfunction "A_A") (pintype "passive"))
      (node (ref "D2") (pin "K") (pinfunction "C_K") (pintype "passive"))
      (node (ref "IC1") (pin "2") (pinfunction "GND_2") (pintype "power_in"))
      (node (ref "IC2") (pin "1") (pinfunction "GND_1") (pintype "power_in"))
      (node (ref "IC3") (pin "10") (pinfunction "+IN_10") (pintype "input"))
      (node (ref "IC3") (pin "3") (pinfunction "+IN_3") (pintype "input"))
      (node (ref "IC3") (pin "5") (pinfunction "+IN_5") (pintype "input"))
      (node (ref "IC4") (pin "7") (pinfunction "B_7") (pintype "passive"))
      (node (ref "IC5") (pin "10") (pinfunction "+IN_10") (pintype "input"))
      (node (ref "IC5") (pin "12") (pinfunction "+IN_12") (pintype "input"))
      (node (ref "IC5") (pin "5") (pinfunction "+IN_5") (pintype "input"))
      (node (ref "J1") (pin "GND1") (pinfunction "2_GND1") (pintype "passive"))
      (node (ref "J1") (pin "GND2") (pinfunction "2_GND2") (pintype "passive"))
      (node (ref "J1") (pin "GND3") (pinfunction "3_GND3") (pintype "passive"))
      (node (ref "J1") (pin "GND4") (pinfunction "3_GND4") (pintype "passive"))
      (node (ref "J1") (pin "GND5") (pinfunction "4_GND5") (pintype "passive"))
      (node (ref "J1") (pin "GND6") (pinfunction "4_GND6") (pintype "passive"))
      (node (ref "J10") (pin "S") (pinfunction "S_S") (pintype "bidirectional"))
      (node (ref "J11") (pin "1") (pinfunction "1_1") (pintype "passive"))
      (node (ref "J11") (pin "2") (pinfunction "2_2") (pintype "passive"))
      (node (ref "J11") (pin "4") (pinfunction "4_4") (pintype "passive"))
      (node (ref "J11") (pin "6") (pinfunction "6_6") (pintype "passive"))
      (node (ref "J13") (pin "P$1") (pinfunction "1_P$1") (pintype "bidirectional"))
      (node (ref "J16") (pin "P$1") (pinfunction "1_P$1") (pintype "bidirectional"))
      (node (ref "J2") (pin "S") (pinfunction "S_S") (pintype "bidirectional"))
      (node (ref "J2") (pin "SW") (pinfunction "SW_SW") (pintype "bidirectional"))
      (node (ref "J3") (pin "S") (pinfunction "S_S") (pintype "bidirectional"))
      (node (ref "J3") (pin "SW") (pinfunction "SW_SW") (pintype "bidirectional"))
      (node (ref "J4") (pin "S") (pinfunction "S_S") (pintype "bidirectional"))
      (node (ref "J4") (pin "SW") (pinfunction "SW_SW") (pintype "bidirectional"))
      (node (ref "J5") (pin "S") (pinfunction "S_S") (pintype "bidirectional"))
      (node (ref "J5") (pin "SW") (pinfunction "SW_SW") (pintype "bidirectional"))
      (node (ref "J6") (pin "S") (pinfunction "S_S") (pintype "bidirectional"))
      (node (ref "J6") (pin "SW") (pinfunction "SW_SW") (pintype "bidirectional"))
      (node (ref "J7") (pin "S") (pinfunction "S_S") (pintype "bidirectional"))
      (node (ref "J9") (pin "1") (pinfunction "1_1") (pintype "passive"))
      (node (ref "J9") (pin "2") (pinfunction "2_2") (pintype "passive"))
      (node (ref "J9") (pin "4") (pinfunction "4_4") (pintype "passive"))
      (node (ref "J9") (pin "6") (pinfunction "6_6") (pintype "passive"))
      (node (ref "M1") (pin "M3") (pinfunction "1_M3") (pintype "bidirectional"))
      (node (ref "M2") (pin "M3") (pinfunction "1_M3") (pintype "bidirectional"))
      (node (ref "M3") (pin "M3") (pinfunction "1_M3") (pintype "bidirectional"))
      (node (ref "M4") (pin "M3") (pinfunction "1_M3") (pintype "bidirectional"))
      (node (ref "M5") (pin "M3") (pinfunction "1_M3") (pintype "bidirectional"))
      (node (ref "M6") (pin "M3") (pinfunction "1_M3") (pintype "bidirectional"))
      (node (ref "M7") (pin "M3") (pinfunction "1_M3") (pintype "bidirectional"))
      (node (ref "M8") (pin "M3") (pinfunction "1_M3") (pintype "bidirectional"))
      (node (ref "R12") (pin "2") (pinfunction "2_2") (pintype "passive"))
      (node (ref "R22") (pin "1") (pinfunction "1_1") (pintype "passive"))
      (node (ref "R26") (pin "3") (pinfunction "3_3") (pintype "passive"))
      (node (ref "R55") (pin "1") (pinfunction "1_1") (pintype "passive"))
      (node (ref "R56") (pin "1") (pinfunction "1_1") (pintype "passive"))
      (node (ref "R57") (pin "1") (pinfunction "1_1") (pintype "passive"))
      (node (ref "R59") (pin "1") (pinfunction "1_1") (pintype "passive"))
      (node (ref "R9") (pin "3") (pinfunction "3_3") (pintype "passive"))
    )
    (net (code "31") (name "MOD1") (class "Default")
      (node (ref "J8") (pin "9") (pinfunction "9_9") (pintype "passive"))
      (node (ref "R1") (pin "1") (pinfunction "1_1") (pintype "passive"))
    )
    (net (code "32") (name "MOD2") (class "Default")
      (node (ref "J8") (pin "4") (pinfunction "4_4") (pintype "passive"))
      (node (ref "R2") (pin "1") (pinfunction "1_1") (pintype "passive"))
    )
    (net (code "33") (name "Net-(C11-+)") (class "Default")
      (node (ref "C11") (pin "1") (pinfunction "+_1") (pintype "passive"))
      (node (ref "IC3") (pin "6") (pinfunction "-IN_6") (pintype "input"))
      (node (ref "IC4") (pin "1") (pinfunction "C_1") (pintype "passive"))
      (node (ref "R13") (pin "1") (pinfunction "1_1") (pintype "passive"))
      (node (ref "R15") (pin "1") (pinfunction "1_1") (pintype "passive"))
    )
    (net (code "34") (name "Net-(C11--)") (class "Default")
      (node (ref "C11") (pin "2") (pinfunction "-_2") (pintype "passive"))
      (node (ref "IC3") (pin "7") (pinfunction "OUT_7") (pintype "output"))
      (node (ref "R14") (pin "1") (pinfunction "1_1") (pintype "passive"))
      (node (ref "R16") (pin "2") (pinfunction "2_2") (pintype "passive"))
    )
    (net (code "35") (name "Net-(C12-+)") (class "Default")
      (node (ref "C12") (pin "1") (pinfunction "+_1") (pintype "passive"))
      (node (ref "IC3") (pin "2") (pinfunction "-IN_2") (pintype "input"))
      (node (ref "IC4") (pin "8") (pinfunction "C_8") (pintype "passive"))
      (node (ref "Q1") (pin "1") (pinfunction "D_1") (pintype "passive"))
    )
    (net (code "36") (name "Net-(C12--)") (class "Default")
      (node (ref "C12") (pin "2") (pinfunction "-_2") (pintype "passive"))
      (node (ref "IC3") (pin "1") (pinfunction "OUT_1") (pintype "output"))
      (node (ref "Q1") (pin "2") (pinfunction "S_2") (pintype "passive"))
      (node (ref "R17") (pin "1") (pinfunction "1_1") (pintype "passive"))
      (node (ref "R23") (pin "1") (pinfunction "1_1") (pintype "passive"))
    )
    (net (code "37") (name "Net-(C13-+)") (class "Default")
      (node (ref "C13") (pin "1") (pinfunction "+_1") (pintype "passive"))
      (node (ref "IC7") (pin "2") (pinfunction "+IN_2") (pintype "input"))
      (node (ref "R17") (pin "2") (pinfunction "2_2") (pintype "passive"))
      (node (ref "R18") (pin "1") (pinfunction "1_1") (pintype "passive"))
    )
    (net (code "38") (name "Net-(C13--)") (class "Default")
      (node (ref "C13") (pin "2") (pinfunction "-_2") (pintype "passive"))
      (node (ref "IC7") (pin "7") (pinfunction "COL_7") (pintype "bidirectional"))
      (node (ref "R18") (pin "2") (pinfunction "2_2") (pintype "passive"))
      (node (ref "R19") (pin "1") (pinfunction "1_1") (pintype "passive"))
      (node (ref "R20") (pin "2") (pinfunction "2_2") (pintype "passive"))
    )
    (net (code "39") (name "Net-(C14--)") (class "Default")
      (node (ref "C14") (pin "2") (pinfunction "-_2") (pintype "passive"))
      (node (ref "IC7") (pin "3") (pinfunction "-IN_3") (pintype "input"))
      (node (ref "R21") (pin "1") (pinfunction "1_1") (pintype "passive"))
      (node (ref "R22") (pin "2") (pinfunction "2_2") (pintype "passive"))
    )
    (net (code "40") (name "Net-(D3-C)") (class "Default")
      (node (ref "D3") (pin "K") (pinfunction "C_K") (pintype "passive"))
      (node (ref "R16") (pin "1") (pinfunction "1_1") (pintype "passive"))
    )
    (net (code "41") (name "Net-(F1-Pad1)") (class "Default")
      (node (ref "F1") (pin "1") (pinfunction "1_1") (pintype "passive"))
      (node (ref "J1") (pin "+12V1") (pinfunction "1_+12V1") (pintype "passive"))
      (node (ref "J1") (pin "+12V2") (pinfunction "1_+12V2") (pintype "passive"))
    )
    (net (code "42") (name "Net-(F2-Pad2)") (class "Default")
      (node (ref "F2") (pin "2") (pinfunction "2_2") (pintype "passive"))
      (node (ref "J1") (pin "-12V1") (pinfunction "5_-12V1") (pintype "passive"))
      (node (ref "J1") (pin "-12V2") (pinfunction "5_-12V2") (pintype "passive"))
    )
    (net (code "43") (name "Net-(IC3C--IN)") (class "Default")
      (node (ref "IC3") (pin "9") (pinfunction "-IN_9") (pintype "input"))
      (node (ref "R1") (pin "2") (pinfunction "2_2") (pintype "passive"))
      (node (ref "R10") (pin "1") (pinfunction "1_1") (pintype "passive"))
      (node (ref "R2") (pin "2") (pinfunction "2_2") (pintype "passive"))
      (node (ref "R3") (pin "1") (pinfunction "1_1") (pintype "passive"))
      (node (ref "R4") (pin "2") (pinfunction "2_2") (pintype "passive"))
      (node (ref "R5") (pin "2") (pinfunction "2_2") (pintype "passive"))
      (node (ref "R6") (pin "2") (pinfunction "2_2") (pintype "passive"))
      (node (ref "R7") (pin "2") (pinfunction "2_2") (pintype "passive"))
      (node (ref "R8") (pin "2") (pinfunction "2_2") (pintype "passive"))
    )
    (net (code "44") (name "Net-(IC3C-OUT)") (class "Default")
      (node (ref "IC3") (pin "8") (pinfunction "OUT_8") (pintype "output"))
      (node (ref "R10") (pin "2") (pinfunction "2_2") (pintype "passive"))
      (node (ref "R11") (pin "1") (pinfunction "1_1") (pintype "passive"))
    )
    (net (code "45") (name "Net-(IC5A-+IN)") (class "Default")
      (node (ref "IC5") (pin "3") (pinfunction "+IN_3") (pintype "input"))
      (node (ref "R30") (pin "2") (pinfunction "2_2") (pintype "passive"))
      (node (ref "R31") (pin "1") (pinfunction "1_1") (pintype "passive"))
    )
    (net (code "46") (name "Net-(IC5A-OUT)") (class "Default")
      (node (ref "IC5") (pin "1") (pinfunction "OUT_1") (pintype "output"))
      (node (ref "R31") (pin "2") (pinfunction "2_2") (pintype "passive"))
      (node (ref "R32") (pin "1") (pinfunction "1_1") (pintype "passive"))
    )
    (net (code "47") (name "Net-(IC5B--IN)") (class "Default")
      (node (ref "IC5") (pin "6") (pinfunction "-IN_6") (pintype "input"))
      (node (ref "R27") (pin "2") (pinfunction "2_2") (pintype "passive"))
      (node (ref "R28") (pin "2") (pinfunction "2_2") (pintype "passive"))
      (node (ref "R29") (pin "1") (pinfunction "1_1") (pintype "passive"))
    )
    (net (code "48") (name "Net-(IC5C--IN)") (class "Default")
      (node (ref "IC5") (pin "9") (pinfunction "-IN_9") (pintype "input"))
      (node (ref "R23") (pin "2") (pinfunction "2_2") (pintype "passive"))
      (node (ref "R24") (pin "2") (pinfunction "2_2") (pintype "passive"))
      (node (ref "R25") (pin "1") (pinfunction "1_1") (pintype "passive"))
    )
    (net (code "49") (name "Net-(IC5D--IN)") (class "Default")
      (node (ref "IC5") (pin "13") (pinfunction "-IN_13") (pintype "input"))
      (node (ref "R32") (pin "2") (pinfunction "2_2") (pintype "passive"))
      (node (ref "R33") (pin "1") (pinfunction "1_1") (pintype "passive"))
    )
    (net (code "50") (name "Net-(J15-Pad3)") (class "Default")
      (node (ref "J15") (pin "3") (pinfunction "3_3") (pintype "passive"))
      (node (ref "R5") (pin "1") (pinfunction "1_1") (pintype "passive"))
    )
    (net (code "51") (name "Net-(Q1-G)") (class "Default")
      (node (ref "Q1") (pin "3") (pinfunction "G_3") (pintype "passive"))
      (node (ref "R20") (pin "1") (pinfunction "1_1") (pintype "passive"))
    )
    (net (code "52") (name "Net-(R11-Pad3)") (class "Default")
      (node (ref "R11") (pin "3") (pinfunction "3_3") (pintype "passive"))
      (node (ref "R12") (pin "1") (pinfunction "1_1") (pintype "passive"))
    )
    (net (code "53") (name "Net-(R24-Pad1)") (class "Default")
      (node (ref "R24") (pin "1") (pinfunction "1_1") (pintype "passive"))
      (node (ref "R26") (pin "2") (pinfunction "2_2") (pintype "passive"))
    )
    (net (code "54") (name "OFFSET") (class "Default")
      (node (ref "J8") (pin "3") (pinfunction "3_3") (pintype "passive"))
      (node (ref "R8") (pin "1") (pinfunction "1_1") (pintype "passive"))
      (node (ref "R9") (pin "2") (pinfunction "2_2") (pintype "passive"))
    )
    (net (code "55") (name "PW") (class "Default")
      (node (ref "IC5") (pin "7") (pinfunction "OUT_7") (pintype "output"))
      (node (ref "J8") (pin "7") (pinfunction "7_7") (pintype "passive"))
      (node (ref "R29") (pin "2") (pinfunction "2_2") (pintype "passive"))
      (node (ref "R30") (pin "1") (pinfunction "1_1") (pintype "passive"))
    )
    (net (code "56") (name "V{slash}OCT") (class "Default")
      (node (ref "IC3") (pin "13") (pinfunction "-IN_13") (pintype "input"))
      (node (ref "IC3") (pin "14") (pinfunction "OUT_14") (pintype "output"))
      (node (ref "J8") (pin "1") (pinfunction "1_1") (pintype "passive"))
      (node (ref "R3") (pin "2") (pinfunction "2_2") (pintype "passive"))
    )
    (net (code "57") (name "unconnected-(IC7A-BAL-Pad5)") (class "Default")
      (node (ref "IC7") (pin "5") (pinfunction "BAL_5") (pintype "input"))
    )
    (net (code "58") (name "unconnected-(IC7A-BAL{slash}STROBE-Pad6)") (class "Default")
      (node (ref "IC7") (pin "6") (pinfunction "BAL/STROBE_6") (pintype "input"))
    )
    (net (code "59") (name "unconnected-(J7-PadSW)") (class "Default")
      (node (ref "J7") (pin "SW") (pinfunction "SW_SW") (pintype "bidirectional"))
    )
    (net (code "60") (name "unconnected-(J10-PadSW)") (class "Default")
      (node (ref "J10") (pin "SW") (pinfunction "SW_SW") (pintype "bidirectional"))
    )
    (net (code "61") (name "unconnected-(J15-Pad1)") (class "Default")
      (node (ref "J15") (pin "1") (pinfunction "1_1") (pintype "passive"))
    )
    (net (code "62") (name "unconnected-(R16-Pad3)") (class "Default")
      (node (ref "R16") (pin "3") (pinfunction "3_3") (pintype "passive"))
    )
  )
)
